# PT1003.net
KiCad netlist of a schematic drawn in Altium Designer
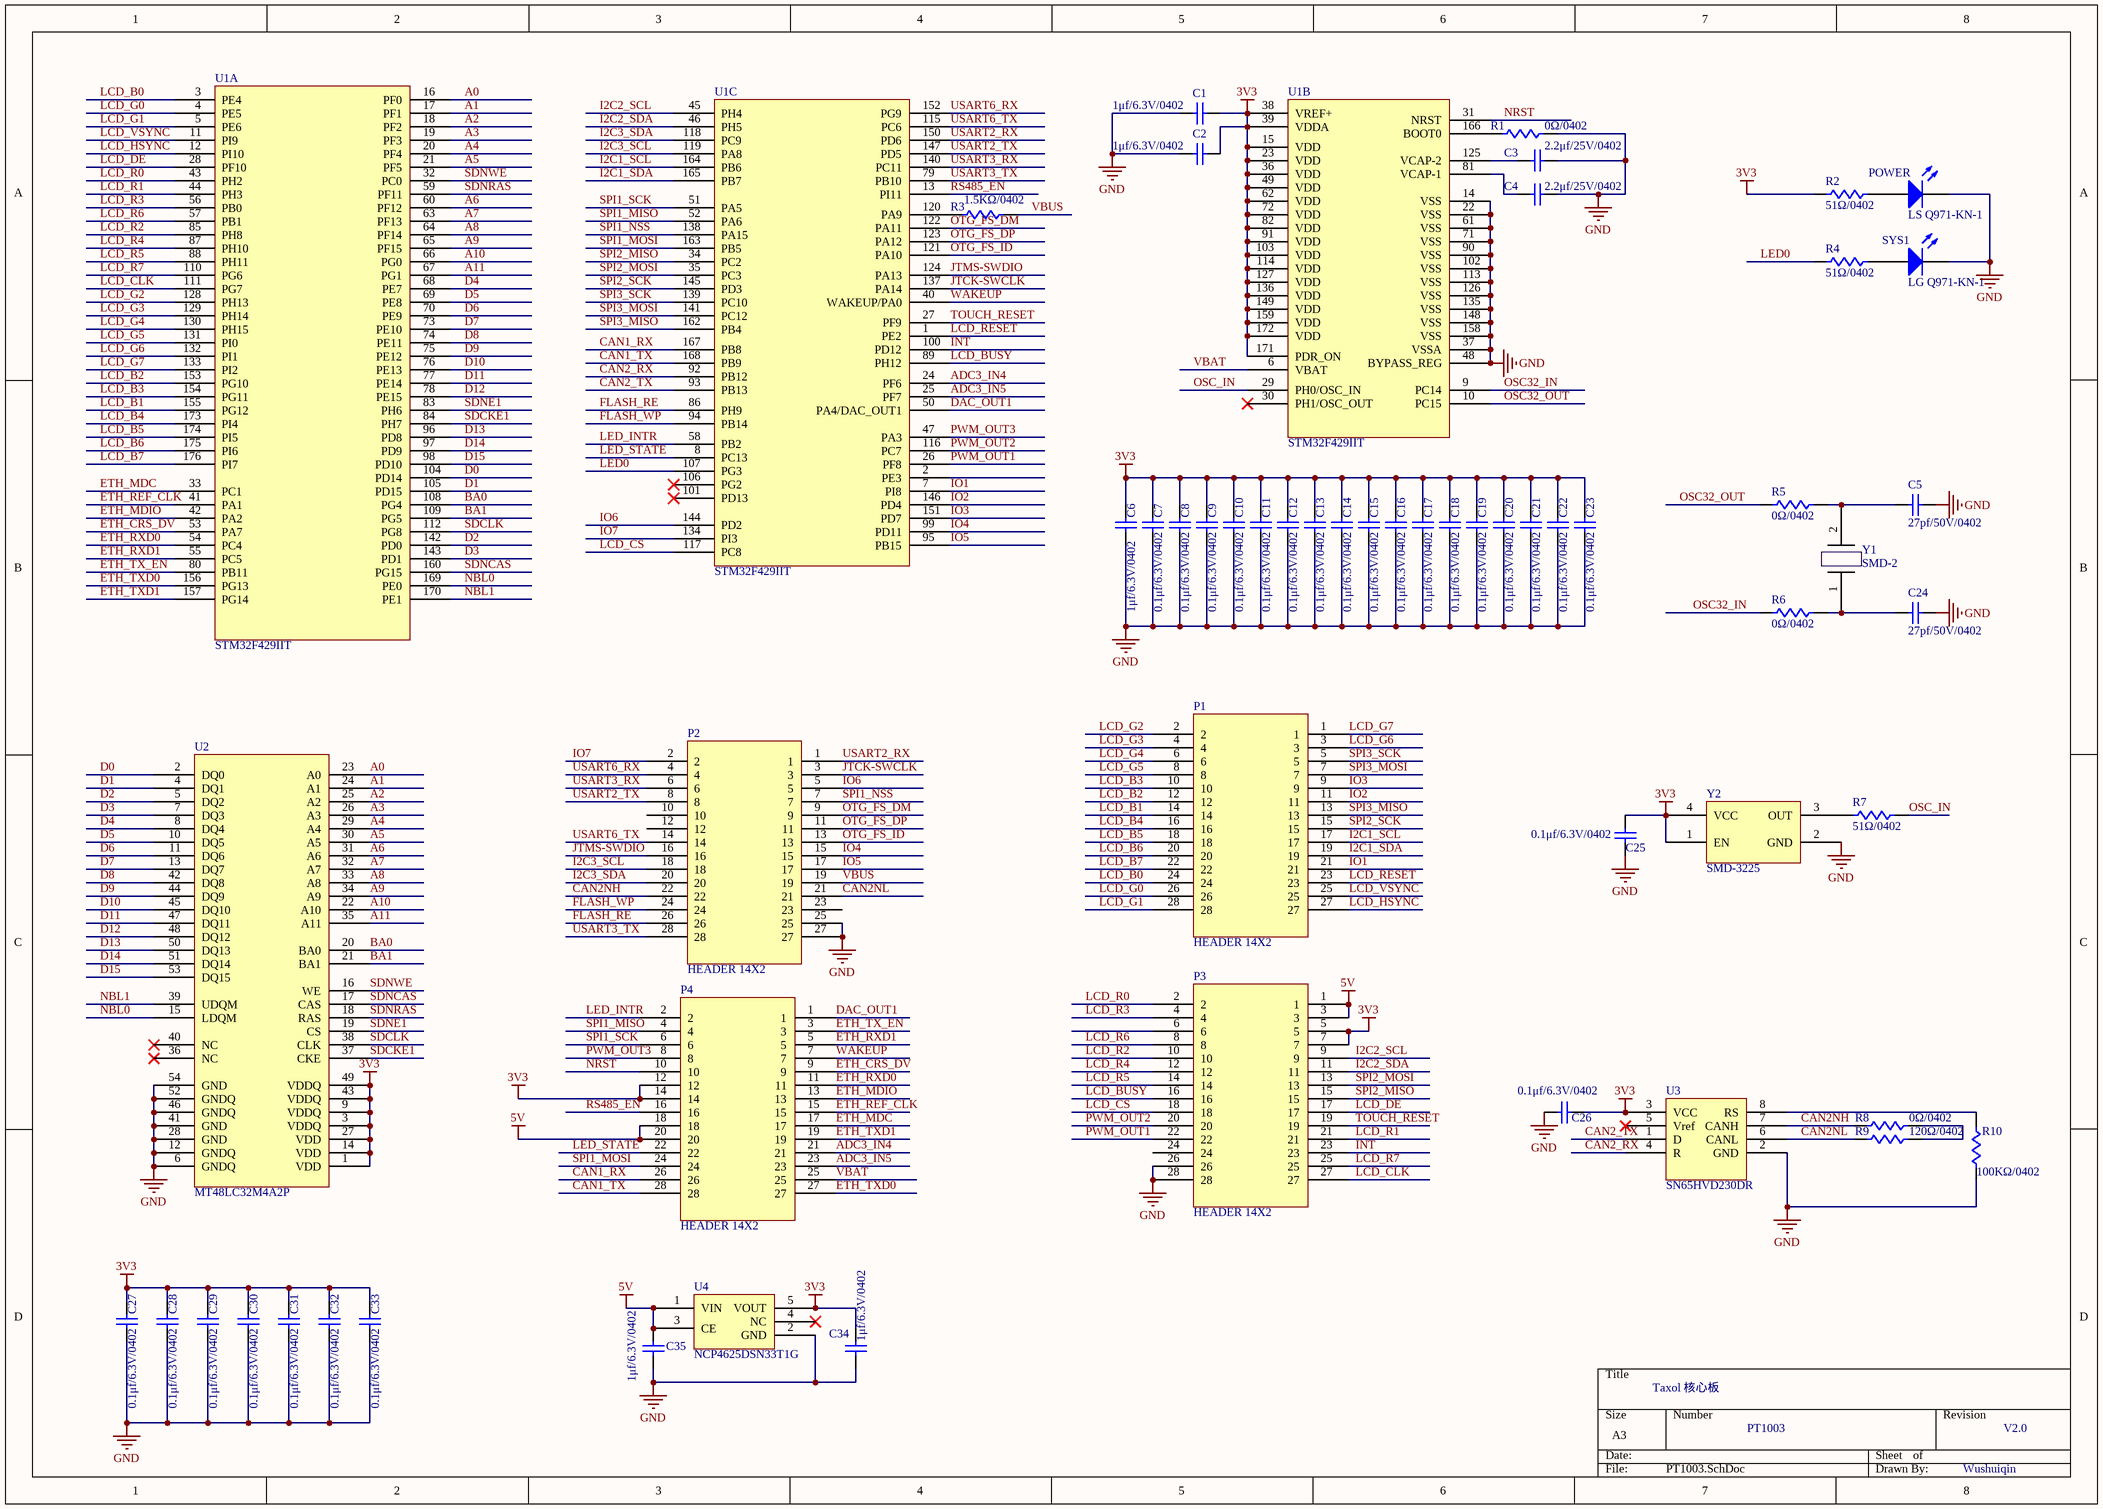
[diagram p0: PT1003.SchDoc]

(export (version "E")
  (design (tool "Eeschema 10.0.6"))
  (components
    (comp (ref "C1")
      (value "1μf/6.3V/0402")
      (footprint "CAPACITOR_0402")
      (fields (field (name "MANUFACTURER") "Murata"))
      (libsource (lib "Taxol") (part "CAPACITOR_0603"))
    )
    (comp (ref "C2")
      (value "1μf/6.3V/0402")
      (footprint "CAPACITOR_0402")
      (fields (field (name "MANUFACTURER") "Murata"))
      (libsource (lib "Taxol") (part "CAPACITOR_0603"))
    )
    (comp (ref "C3")
      (value "2.2μf/25V/0402")
      (footprint "CAPACITOR_0402")
      (fields (field (name "MANUFACTURER") "TDK"))
      (libsource (lib "Taxol") (part "CAPACITOR_0603"))
    )
    (comp (ref "C4")
      (value "2.2μf/25V/0402")
      (footprint "CAPACITOR_0402")
      (fields (field (name "MANUFACTURER") "TDK"))
      (libsource (lib "Taxol") (part "CAPACITOR_0603"))
    )
    (comp (ref "C5")
      (value "27pf/50V/0402")
      (footprint "CAPACITOR_0402")
      (fields (field (name "MANUFACTURER") "AVX"))
      (libsource (lib "PT1003") (part "CAPACITOR"))
    )
    (comp (ref "C6")
      (value "1μf/6.3V/0402")
      (footprint "CAPACITOR_0402")
      (fields (field (name "MANUFACTURER") "Murata"))
      (libsource (lib "Taxol") (part "CAPACITOR_0603"))
    )
    (comp (ref "C7")
      (value "0.1μf/6.3V/0402")
      (footprint "CAPACITOR_0402")
      (fields (field (name "MANUFACTURER") "TDK"))
      (libsource (lib "Taxol") (part "CAPACITOR_0603"))
    )
    (comp (ref "C8")
      (value "0.1μf/6.3V/0402")
      (footprint "CAPACITOR_0402")
      (fields (field (name "MANUFACTURER") "TDK"))
      (libsource (lib "Taxol") (part "CAPACITOR_0603"))
    )
    (comp (ref "C9")
      (value "0.1μf/6.3V/0402")
      (footprint "CAPACITOR_0402")
      (fields (field (name "MANUFACTURER") "TDK"))
      (libsource (lib "Taxol") (part "CAPACITOR_0603"))
    )
    (comp (ref "C10")
      (value "0.1μf/6.3V/0402")
      (footprint "CAPACITOR_0402")
      (fields (field (name "MANUFACTURER") "TDK"))
      (libsource (lib "Taxol") (part "CAPACITOR_0603"))
    )
    (comp (ref "C11")
      (value "0.1μf/6.3V/0402")
      (footprint "CAPACITOR_0402")
      (fields (field (name "MANUFACTURER") "TDK"))
      (libsource (lib "Taxol") (part "CAPACITOR_0603"))
    )
    (comp (ref "C12")
      (value "0.1μf/6.3V/0402")
      (footprint "CAPACITOR_0402")
      (fields (field (name "MANUFACTURER") "TDK"))
      (libsource (lib "Taxol") (part "CAPACITOR_0603"))
    )
    (comp (ref "C13")
      (value "0.1μf/6.3V/0402")
      (footprint "CAPACITOR_0402")
      (fields (field (name "MANUFACTURER") "TDK"))
      (libsource (lib "Taxol") (part "CAPACITOR_0603"))
    )
    (comp (ref "C14")
      (value "0.1μf/6.3V/0402")
      (footprint "CAPACITOR_0402")
      (fields (field (name "MANUFACTURER") "TDK"))
      (libsource (lib "Taxol") (part "CAPACITOR_0603"))
    )
    (comp (ref "C15")
      (value "0.1μf/6.3V/0402")
      (footprint "CAPACITOR_0402")
      (fields (field (name "MANUFACTURER") "TDK"))
      (libsource (lib "Taxol") (part "CAPACITOR_0603"))
    )
    (comp (ref "C16")
      (value "0.1μf/6.3V/0402")
      (footprint "CAPACITOR_0402")
      (fields (field (name "MANUFACTURER") "TDK"))
      (libsource (lib "Taxol") (part "CAPACITOR_0603"))
    )
    (comp (ref "C17")
      (value "0.1μf/6.3V/0402")
      (footprint "CAPACITOR_0402")
      (fields (field (name "MANUFACTURER") "TDK"))
      (libsource (lib "Taxol") (part "CAPACITOR_0603"))
    )
    (comp (ref "C18")
      (value "0.1μf/6.3V/0402")
      (footprint "CAPACITOR_0402")
      (fields (field (name "MANUFACTURER") "TDK"))
      (libsource (lib "Taxol") (part "CAPACITOR_0603"))
    )
    (comp (ref "C19")
      (value "0.1μf/6.3V/0402")
      (footprint "CAPACITOR_0402")
      (fields (field (name "MANUFACTURER") "TDK"))
      (libsource (lib "Taxol") (part "CAPACITOR_0603"))
    )
    (comp (ref "C20")
      (value "0.1μf/6.3V/0402")
      (footprint "CAPACITOR_0402")
      (fields (field (name "MANUFACTURER") "TDK"))
      (libsource (lib "Taxol") (part "CAPACITOR_0603"))
    )
    (comp (ref "C21")
      (value "0.1μf/6.3V/0402")
      (footprint "CAPACITOR_0402")
      (fields (field (name "MANUFACTURER") "TDK"))
      (libsource (lib "Taxol") (part "CAPACITOR_0603"))
    )
    (comp (ref "C22")
      (value "0.1μf/6.3V/0402")
      (footprint "CAPACITOR_0402")
      (fields (field (name "MANUFACTURER") "TDK"))
      (libsource (lib "Taxol") (part "CAPACITOR_0603"))
    )
    (comp (ref "C23")
      (value "0.1μf/6.3V/0402")
      (footprint "CAPACITOR_0402")
      (fields (field (name "MANUFACTURER") "TDK"))
      (libsource (lib "Taxol") (part "CAPACITOR_0603"))
    )
    (comp (ref "C24")
      (value "27pf/50V/0402")
      (footprint "CAPACITOR_0402")
      (fields (field (name "MANUFACTURER") "AVX"))
      (libsource (lib "PT1003") (part "CAPACITOR"))
    )
    (comp (ref "C25")
      (value "0.1μf/6.3V/0402")
      (footprint "CAPACITOR_0402")
      (fields (field (name "MANUFACTURER") "TDK"))
      (libsource (lib "Taxol") (part "CAPACITOR_0603"))
    )
    (comp (ref "C26")
      (value "0.1μf/6.3V/0402")
      (footprint "CAPACITOR_0402")
      (fields (field (name "MANUFACTURER") "TDK"))
      (libsource (lib "Taxol") (part "CAPACITOR_0603"))
    )
    (comp (ref "C27")
      (value "0.1μf/6.3V/0402")
      (footprint "CAPACITOR_0402")
      (fields (field (name "MANUFACTURER") "TDK"))
      (libsource (lib "Taxol") (part "CAPACITOR_0603"))
    )
    (comp (ref "C28")
      (value "0.1μf/6.3V/0402")
      (footprint "CAPACITOR_0402")
      (fields (field (name "MANUFACTURER") "TDK"))
      (libsource (lib "Taxol") (part "CAPACITOR_0603"))
    )
    (comp (ref "C29")
      (value "0.1μf/6.3V/0402")
      (footprint "CAPACITOR_0402")
      (fields (field (name "MANUFACTURER") "TDK"))
      (libsource (lib "Taxol") (part "CAPACITOR_0603"))
    )
    (comp (ref "C30")
      (value "0.1μf/6.3V/0402")
      (footprint "CAPACITOR_0402")
      (fields (field (name "MANUFACTURER") "TDK"))
      (libsource (lib "Taxol") (part "CAPACITOR_0603"))
    )
    (comp (ref "C31")
      (value "0.1μf/6.3V/0402")
      (footprint "CAPACITOR_0402")
      (fields (field (name "MANUFACTURER") "TDK"))
      (libsource (lib "Taxol") (part "CAPACITOR_0603"))
    )
    (comp (ref "C32")
      (value "0.1μf/6.3V/0402")
      (footprint "CAPACITOR_0402")
      (fields (field (name "MANUFACTURER") "TDK"))
      (libsource (lib "Taxol") (part "CAPACITOR_0603"))
    )
    (comp (ref "C33")
      (value "0.1μf/6.3V/0402")
      (footprint "CAPACITOR_0402")
      (fields (field (name "MANUFACTURER") "TDK"))
      (libsource (lib "Taxol") (part "CAPACITOR_0603"))
    )
    (comp (ref "C34")
      (value "1μf/6.3V/0402")
      (footprint "CAPACITOR_0402")
      (fields (field (name "MANUFACTURER") "Murata"))
      (libsource (lib "Taxol") (part "CAPACITOR_0603"))
    )
    (comp (ref "C35")
      (value "1μf/6.3V/0402")
      (footprint "CAPACITOR_0402")
      (fields (field (name "MANUFACTURER") "Murata"))
      (libsource (lib "Taxol") (part "CAPACITOR_0603"))
    )
    (comp (ref "P1") (value "HEADER 14X2") (footprint "PIN") (libsource (lib "PT1003") (part "PIN")))
    (comp (ref "P2") (value "HEADER 14X2") (footprint "PIN_1") (libsource (lib "PT1003") (part "PIN_1")))
    (comp (ref "P3") (value "HEADER 14X2") (footprint "PIN") (libsource (lib "PT1003") (part "PIN")))
    (comp (ref "P4") (value "HEADER 14X2") (footprint "PIN_1") (libsource (lib "PT1003") (part "PIN_1")))
    (comp (ref "POWER")
      (value "LS Q971-KN-1")
      (footprint "LED")
      (description "LED_G")
      (fields (field (name "MANUFACTURER") "OSRAM"))
      (libsource (lib "Taxol") (part "LED"))
    )
    (comp (ref "R1")
      (value "0Ω/0402")
      (footprint "RESSISTANCE_0402")
      (fields (field (name "MANUFACTURER") "VISHAY"))
      (libsource (lib "Taxol") (part "RESISTANCE"))
    )
    (comp (ref "R2")
      (value "51Ω/0402")
      (footprint "RESSISTANCE_0402")
      (fields (field (name "MANUFACTURER") "VISHAY"))
      (libsource (lib "Taxol") (part "RESISTANCE"))
    )
    (comp (ref "R3")
      (value "1.5KΩ/0402")
      (footprint "RESSISTANCE_0402")
      (fields (field (name "MANUFACTURER") "Vishay"))
      (libsource (lib "PT1003") (part "RESISTANCE"))
    )
    (comp (ref "R4")
      (value "51Ω/0402")
      (footprint "RESSISTANCE_0402")
      (fields (field (name "MANUFACTURER") "VISHAY"))
      (libsource (lib "Taxol") (part "RESISTANCE"))
    )
    (comp (ref "R5")
      (value "0Ω/0402")
      (footprint "RESSISTANCE_0402")
      (fields (field (name "MANUFACTURER") "VISHAY"))
      (libsource (lib "Taxol") (part "RESISTANCE"))
    )
    (comp (ref "R6")
      (value "0Ω/0402")
      (footprint "RESSISTANCE_0402")
      (fields (field (name "MANUFACTURER") "Vishay"))
      (libsource (lib "PT1003") (part "RESISTANCE"))
    )
    (comp (ref "R7")
      (value "51Ω/0402")
      (footprint "RESSISTANCE_0402")
      (fields (field (name "MANUFACTURER") "VISHAY"))
      (libsource (lib "Taxol") (part "RESISTANCE"))
    )
    (comp (ref "R8")
      (value "0Ω/0402")
      (footprint "RESSISTANCE_0402")
      (fields (field (name "MANUFACTURER") "VISHAY"))
      (libsource (lib "PT1003") (part "RESISTANCE"))
    )
    (comp (ref "R9")
      (value "120Ω/0402")
      (footprint "RESSISTANCE_0402")
      (fields (field (name "MANUFACTURER") "Vishay"))
      (libsource (lib "PT1003") (part "RESISTANCE"))
    )
    (comp (ref "R10")
      (value "100KΩ/0402")
      (footprint "RESSISTANCE_0402")
      (fields (field (name "MANUFACTURER") "VISHAY"))
      (libsource (lib "Taxol") (part "RESISTANCE"))
    )
    (comp (ref "SYS1")
      (value "LG Q971-KN-1")
      (footprint "LED")
      (description "LED_G")
      (fields (field (name "MANUFACTURER") "OSRAM"))
      (libsource (lib "Taxol") (part "LED"))
    )
    (comp (ref "U1")
      (value "STM32F429IIT")
      (footprint "STM32F429IIT")
      (fields (field (name "MANUFACTURER") "ST"))
      (libsource (lib "PT1003") (part "STM32F429IIT"))
    )
    (comp (ref "U2")
      (value "MT48LC32M4A2P")
      (footprint "IS42S16400J")
      (description "SDRAM")
      (fields (field (name "MANUFACTURER") "MICRON"))
      (libsource (lib "PT1003") (part "IS42S16400J"))
    )
    (comp (ref "U3")
      (value "SN65HVD230DR")
      (footprint "SN65HVD230")
      (description "CAN")
      (fields (field (name "MANUFACTURER") "TEXAS INSTRUMENTS"))
      (libsource (lib "Taxol") (part "SN65HVD230DR"))
    )
    (comp (ref "U4")
      (value "NCP4625DSN33T1G")
      (footprint "NCP4625DSN33T1G")
      (fields (field (name "MANUFACTURER") "ON"))
      (libsource (lib "PT1003") (part "NCP4625DSN33T1G"))
    )
    (comp (ref "Y1")
      (value "SMD-2")
      (footprint "SMD-2")
      (fields (field (name "MANUFACTURER") "MICRO CRYSTAL SWITZERLAND"))
      (libsource (lib "PT1003") (part "CC7V-TIA"))
    )
    (comp (ref "Y2")
      (value "SMD-3225")
      (footprint "X032")
      (description "4-Pin")
      (fields (field (name "MANUFACTURER") "深圳市金丰瑞电子有限公司"))
      (libsource (lib "Taxol") (part "X075_8MHZ"))
    )
  )
  (nets
    (net (code "1") (name "/A0") (class "Default")
      (node (ref "U1") (pin "16") (pinfunction "PF0_16") (pintype "passive"))
      (node (ref "U2") (pin "23") (pinfunction "A0_23") (pintype "passive"))
    )
    (net (code "2") (name "/A1") (class "Default")
      (node (ref "U1") (pin "17") (pinfunction "PF1_17") (pintype "passive"))
      (node (ref "U2") (pin "24") (pinfunction "A1_24") (pintype "passive"))
    )
    (net (code "3") (name "/A2") (class "Default")
      (node (ref "U1") (pin "18") (pinfunction "PF2_18") (pintype "passive"))
      (node (ref "U2") (pin "25") (pinfunction "A2_25") (pintype "passive"))
    )
    (net (code "4") (name "/A3") (class "Default")
      (node (ref "U1") (pin "19") (pinfunction "PF3_19") (pintype "passive"))
      (node (ref "U2") (pin "26") (pinfunction "A3_26") (pintype "passive"))
    )
    (net (code "5") (name "/A4") (class "Default")
      (node (ref "U1") (pin "20") (pinfunction "PF4_20") (pintype "passive"))
      (node (ref "U2") (pin "29") (pinfunction "A4_29") (pintype "passive"))
    )
    (net (code "6") (name "/A5") (class "Default")
      (node (ref "U1") (pin "21") (pinfunction "PF5_21") (pintype "passive"))
      (node (ref "U2") (pin "30") (pinfunction "A5_30") (pintype "passive"))
    )
    (net (code "7") (name "/A6") (class "Default")
      (node (ref "U1") (pin "60") (pinfunction "PF12_60") (pintype "passive"))
      (node (ref "U2") (pin "31") (pinfunction "A6_31") (pintype "passive"))
    )
    (net (code "8") (name "/A7") (class "Default")
      (node (ref "U1") (pin "63") (pinfunction "PF13_63") (pintype "passive"))
      (node (ref "U2") (pin "32") (pinfunction "A7_32") (pintype "passive"))
    )
    (net (code "9") (name "/A8") (class "Default")
      (node (ref "U1") (pin "64") (pinfunction "PF14_64") (pintype "passive"))
      (node (ref "U2") (pin "33") (pinfunction "A8_33") (pintype "passive"))
    )
    (net (code "10") (name "/A9") (class "Default")
      (node (ref "U1") (pin "65") (pinfunction "PF15_65") (pintype "passive"))
      (node (ref "U2") (pin "34") (pinfunction "A9_34") (pintype "passive"))
    )
    (net (code "11") (name "/A10") (class "Default")
      (node (ref "U1") (pin "66") (pinfunction "PG0_66") (pintype "passive"))
      (node (ref "U2") (pin "22") (pinfunction "A10_22") (pintype "passive"))
    )
    (net (code "12") (name "/A11") (class "Default")
      (node (ref "U1") (pin "67") (pinfunction "PG1_67") (pintype "passive"))
      (node (ref "U2") (pin "35") (pinfunction "A11_35") (pintype "passive"))
    )
    (net (code "13") (name "/ADC3_IN4") (class "Default")
      (node (ref "P4") (pin "21") (pinfunction "21_21") (pintype "passive"))
      (node (ref "U1") (pin "24") (pinfunction "PF6_24") (pintype "passive"))
    )
    (net (code "14") (name "/ADC3_IN5") (class "Default")
      (node (ref "P4") (pin "23") (pinfunction "23_23") (pintype "passive"))
      (node (ref "U1") (pin "25") (pinfunction "PF7_25") (pintype "passive"))
    )
    (net (code "15") (name "/BA0") (class "Default")
      (node (ref "U1") (pin "108") (pinfunction "PG4_108") (pintype "passive"))
      (node (ref "U2") (pin "20") (pinfunction "BA0_20") (pintype "passive"))
    )
    (net (code "16") (name "/BA1") (class "Default")
      (node (ref "U1") (pin "109") (pinfunction "PG5_109") (pintype "passive"))
      (node (ref "U2") (pin "21") (pinfunction "BA1_21") (pintype "passive"))
    )
    (net (code "17") (name "/CAN1_RX") (class "Default")
      (node (ref "P4") (pin "26") (pinfunction "26_26") (pintype "passive"))
      (node (ref "U1") (pin "167") (pinfunction "PB8_167") (pintype "passive"))
    )
    (net (code "18") (name "/CAN1_TX") (class "Default")
      (node (ref "P4") (pin "28") (pinfunction "28_28") (pintype "passive"))
      (node (ref "U1") (pin "168") (pinfunction "PB9_168") (pintype "passive"))
    )
    (net (code "19") (name "/CAN2NH") (class "Default")
      (node (ref "P2") (pin "22") (pinfunction "22_22") (pintype "passive"))
      (node (ref "R8") (pin "1") (pinfunction "1_1") (pintype "passive"))
      (node (ref "U3") (pin "7") (pinfunction "CANH_7") (pintype "passive"))
    )
    (net (code "20") (name "/CAN2NL") (class "Default")
      (node (ref "P2") (pin "21") (pinfunction "21_21") (pintype "passive"))
      (node (ref "R9") (pin "1") (pinfunction "1_1") (pintype "passive"))
      (node (ref "U3") (pin "6") (pinfunction "CANL_6") (pintype "passive"))
    )
    (net (code "21") (name "/CAN2_RX") (class "Default")
      (node (ref "U1") (pin "92") (pinfunction "PB12_92") (pintype "passive"))
      (node (ref "U3") (pin "4") (pinfunction "R_4") (pintype "passive"))
    )
    (net (code "22") (name "/CAN2_TX") (class "Default")
      (node (ref "U1") (pin "93") (pinfunction "PB13_93") (pintype "passive"))
      (node (ref "U3") (pin "1") (pinfunction "D_1") (pintype "passive"))
    )
    (net (code "23") (name "/D0") (class "Default")
      (node (ref "U1") (pin "104") (pinfunction "PD14_104") (pintype "passive"))
      (node (ref "U2") (pin "2") (pinfunction "DQ0_2") (pintype "passive"))
    )
    (net (code "24") (name "/D1") (class "Default")
      (node (ref "U1") (pin "105") (pinfunction "PD15_105") (pintype "passive"))
      (node (ref "U2") (pin "4") (pinfunction "DQ1_4") (pintype "passive"))
    )
    (net (code "25") (name "/D2") (class "Default")
      (node (ref "U1") (pin "142") (pinfunction "PD0_142") (pintype "passive"))
      (node (ref "U2") (pin "5") (pinfunction "DQ2_5") (pintype "passive"))
    )
    (net (code "26") (name "/D3") (class "Default")
      (node (ref "U1") (pin "143") (pinfunction "PD1_143") (pintype "passive"))
      (node (ref "U2") (pin "7") (pinfunction "DQ3_7") (pintype "passive"))
    )
    (net (code "27") (name "/D4") (class "Default")
      (node (ref "U1") (pin "68") (pinfunction "PE7_68") (pintype "passive"))
      (node (ref "U2") (pin "8") (pinfunction "DQ4_8") (pintype "passive"))
    )
    (net (code "28") (name "/D5") (class "Default")
      (node (ref "U1") (pin "69") (pinfunction "PE8_69") (pintype "passive"))
      (node (ref "U2") (pin "10") (pinfunction "DQ5_10") (pintype "passive"))
    )
    (net (code "29") (name "/D6") (class "Default")
      (node (ref "U1") (pin "70") (pinfunction "PE9_70") (pintype "passive"))
      (node (ref "U2") (pin "11") (pinfunction "DQ6_11") (pintype "passive"))
    )
    (net (code "30") (name "/D7") (class "Default")
      (node (ref "U1") (pin "73") (pinfunction "PE10_73") (pintype "passive"))
      (node (ref "U2") (pin "13") (pinfunction "DQ7_13") (pintype "passive"))
    )
    (net (code "31") (name "/D8") (class "Default")
      (node (ref "U1") (pin "74") (pinfunction "PE11_74") (pintype "passive"))
      (node (ref "U2") (pin "42") (pinfunction "DQ8_42") (pintype "passive"))
    )
    (net (code "32") (name "/D9") (class "Default")
      (node (ref "U1") (pin "75") (pinfunction "PE12_75") (pintype "passive"))
      (node (ref "U2") (pin "44") (pinfunction "DQ9_44") (pintype "passive"))
    )
    (net (code "33") (name "/D10") (class "Default")
      (node (ref "U1") (pin "76") (pinfunction "PE13_76") (pintype "passive"))
      (node (ref "U2") (pin "45") (pinfunction "DQ10_45") (pintype "passive"))
    )
    (net (code "34") (name "/D11") (class "Default")
      (node (ref "U1") (pin "77") (pinfunction "PE14_77") (pintype "passive"))
      (node (ref "U2") (pin "47") (pinfunction "DQ11_47") (pintype "passive"))
    )
    (net (code "35") (name "/D12") (class "Default")
      (node (ref "U1") (pin "78") (pinfunction "PE15_78") (pintype "passive"))
      (node (ref "U2") (pin "48") (pinfunction "DQ12_48") (pintype "passive"))
    )
    (net (code "36") (name "/D13") (class "Default")
      (node (ref "U1") (pin "96") (pinfunction "PD8_96") (pintype "passive"))
      (node (ref "U2") (pin "50") (pinfunction "DQ13_50") (pintype "passive"))
    )
    (net (code "37") (name "/D14") (class "Default")
      (node (ref "U1") (pin "97") (pinfunction "PD9_97") (pintype "passive"))
      (node (ref "U2") (pin "51") (pinfunction "DQ14_51") (pintype "passive"))
    )
    (net (code "38") (name "/D15") (class "Default")
      (node (ref "U1") (pin "98") (pinfunction "PD10_98") (pintype "passive"))
      (node (ref "U2") (pin "53") (pinfunction "DQ15_53") (pintype "passive"))
    )
    (net (code "39") (name "/DAC_OUT1") (class "Default")
      (node (ref "P4") (pin "1") (pinfunction "1_1") (pintype "passive"))
      (node (ref "U1") (pin "50") (pinfunction "PA4/DAC_OUT1_50") (pintype "passive"))
    )
    (net (code "40") (name "/ETH_CRS_DV") (class "Default")
      (node (ref "P4") (pin "9") (pinfunction "9_9") (pintype "passive"))
      (node (ref "U1") (pin "53") (pinfunction "PA7_53") (pintype "passive"))
    )
    (net (code "41") (name "/ETH_MDC") (class "Default")
      (node (ref "P4") (pin "17") (pinfunction "17_17") (pintype "passive"))
      (node (ref "U1") (pin "33") (pinfunction "PC1_33") (pintype "passive"))
    )
    (net (code "42") (name "/ETH_MDIO") (class "Default")
      (node (ref "P4") (pin "13") (pinfunction "13_13") (pintype "passive"))
      (node (ref "U1") (pin "42") (pinfunction "PA2_42") (pintype "passive"))
    )
    (net (code "43") (name "/ETH_REF_CLK") (class "Default")
      (node (ref "P4") (pin "15") (pinfunction "15_15") (pintype "passive"))
      (node (ref "U1") (pin "41") (pinfunction "PA1_41") (pintype "passive"))
    )
    (net (code "44") (name "/ETH_RXD0") (class "Default")
      (node (ref "P4") (pin "11") (pinfunction "11_11") (pintype "passive"))
      (node (ref "U1") (pin "54") (pinfunction "PC4_54") (pintype "passive"))
    )
    (net (code "45") (name "/ETH_RXD1") (class "Default")
      (node (ref "P4") (pin "5") (pinfunction "5_5") (pintype "passive"))
      (node (ref "U1") (pin "55") (pinfunction "PC5_55") (pintype "passive"))
    )
    (net (code "46") (name "/ETH_TXD0") (class "Default")
      (node (ref "P4") (pin "27") (pinfunction "27_27") (pintype "passive"))
      (node (ref "U1") (pin "156") (pinfunction "PG13_156") (pintype "passive"))
    )
    (net (code "47") (name "/ETH_TXD1") (class "Default")
      (node (ref "P4") (pin "19") (pinfunction "19_19") (pintype "passive"))
      (node (ref "U1") (pin "157") (pinfunction "PG14_157") (pintype "passive"))
    )
    (net (code "48") (name "/ETH_TX_EN") (class "Default")
      (node (ref "P4") (pin "3") (pinfunction "3_3") (pintype "passive"))
      (node (ref "U1") (pin "80") (pinfunction "PB11_80") (pintype "passive"))
    )
    (net (code "49") (name "/FLASH_RE") (class "Default")
      (node (ref "P2") (pin "26") (pinfunction "26_26") (pintype "passive"))
      (node (ref "U1") (pin "86") (pinfunction "PH9_86") (pintype "passive"))
    )
    (net (code "50") (name "/FLASH_WP") (class "Default")
      (node (ref "P2") (pin "24") (pinfunction "24_24") (pintype "passive"))
      (node (ref "U1") (pin "94") (pinfunction "PB14_94") (pintype "passive"))
    )
    (net (code "51") (name "/I2C1_SCL") (class "Default")
      (node (ref "P1") (pin "17") (pinfunction "17_17") (pintype "passive"))
      (node (ref "U1") (pin "164") (pinfunction "PB6_164") (pintype "passive"))
    )
    (net (code "52") (name "/I2C1_SDA") (class "Default")
      (node (ref "P1") (pin "19") (pinfunction "19_19") (pintype "passive"))
      (node (ref "U1") (pin "165") (pinfunction "PB7_165") (pintype "passive"))
    )
    (net (code "53") (name "/I2C2_SCL") (class "Default")
      (node (ref "P3") (pin "9") (pinfunction "9_9") (pintype "passive"))
      (node (ref "U1") (pin "45") (pinfunction "PH4_45") (pintype "passive"))
    )
    (net (code "54") (name "/I2C2_SDA") (class "Default")
      (node (ref "P3") (pin "11") (pinfunction "11_11") (pintype "passive"))
      (node (ref "U1") (pin "46") (pinfunction "PH5_46") (pintype "passive"))
    )
    (net (code "55") (name "/I2C3_SCL") (class "Default")
      (node (ref "P2") (pin "18") (pinfunction "18_18") (pintype "passive"))
      (node (ref "U1") (pin "119") (pinfunction "PA8_119") (pintype "passive"))
    )
    (net (code "56") (name "/I2C3_SDA") (class "Default")
      (node (ref "P2") (pin "20") (pinfunction "20_20") (pintype "passive"))
      (node (ref "U1") (pin "118") (pinfunction "PC9_118") (pintype "passive"))
    )
    (net (code "57") (name "/INT") (class "Default")
      (node (ref "P3") (pin "23") (pinfunction "23_23") (pintype "passive"))
      (node (ref "U1") (pin "100") (pinfunction "PD12_100") (pintype "passive"))
    )
    (net (code "58") (name "/IO1") (class "Default")
      (node (ref "P1") (pin "21") (pinfunction "21_21") (pintype "passive"))
      (node (ref "U1") (pin "7") (pinfunction "PI8_7") (pintype "passive"))
    )
    (net (code "59") (name "/IO2") (class "Default")
      (node (ref "P1") (pin "11") (pinfunction "11_11") (pintype "passive"))
      (node (ref "U1") (pin "146") (pinfunction "PD4_146") (pintype "passive"))
    )
    (net (code "60") (name "/IO3") (class "Default")
      (node (ref "P1") (pin "9") (pinfunction "9_9") (pintype "passive"))
      (node (ref "U1") (pin "151") (pinfunction "PD7_151") (pintype "passive"))
    )
    (net (code "61") (name "/IO4") (class "Default")
      (node (ref "P2") (pin "15") (pinfunction "15_15") (pintype "passive"))
      (node (ref "U1") (pin "99") (pinfunction "PD11_99") (pintype "passive"))
    )
    (net (code "62") (name "/IO5") (class "Default")
      (node (ref "P2") (pin "17") (pinfunction "17_17") (pintype "passive"))
      (node (ref "U1") (pin "95") (pinfunction "PB15_95") (pintype "passive"))
    )
    (net (code "63") (name "/IO6") (class "Default")
      (node (ref "P2") (pin "5") (pinfunction "5_5") (pintype "passive"))
      (node (ref "U1") (pin "144") (pinfunction "PD2_144") (pintype "passive"))
    )
    (net (code "64") (name "/IO7") (class "Default")
      (node (ref "P2") (pin "2") (pinfunction "2_2") (pintype "passive"))
      (node (ref "U1") (pin "134") (pinfunction "PI3_134") (pintype "passive"))
    )
    (net (code "65") (name "/JTCK-SWCLK") (class "Default")
      (node (ref "P2") (pin "3") (pinfunction "3_3") (pintype "passive"))
      (node (ref "U1") (pin "137") (pinfunction "PA14_137") (pintype "passive"))
    )
    (net (code "66") (name "/JTMS-SWDIO") (class "Default")
      (node (ref "P2") (pin "16") (pinfunction "16_16") (pintype "passive"))
      (node (ref "U1") (pin "124") (pinfunction "PA13_124") (pintype "passive"))
    )
    (net (code "67") (name "/LCD_B0") (class "Default")
      (node (ref "P1") (pin "24") (pinfunction "24_24") (pintype "passive"))
      (node (ref "U1") (pin "3") (pinfunction "PE4_3") (pintype "passive"))
    )
    (net (code "68") (name "/LCD_B1") (class "Default")
      (node (ref "P1") (pin "14") (pinfunction "14_14") (pintype "passive"))
      (node (ref "U1") (pin "155") (pinfunction "PG12_155") (pintype "passive"))
    )
    (net (code "69") (name "/LCD_B2") (class "Default")
      (node (ref "P1") (pin "12") (pinfunction "12_12") (pintype "passive"))
      (node (ref "U1") (pin "153") (pinfunction "PG10_153") (pintype "passive"))
    )
    (net (code "70") (name "/LCD_B3") (class "Default")
      (node (ref "P1") (pin "10") (pinfunction "10_10") (pintype "passive"))
      (node (ref "U1") (pin "154") (pinfunction "PG11_154") (pintype "passive"))
    )
    (net (code "71") (name "/LCD_B4") (class "Default")
      (node (ref "P1") (pin "16") (pinfunction "16_16") (pintype "passive"))
      (node (ref "U1") (pin "173") (pinfunction "PI4_173") (pintype "passive"))
    )
    (net (code "72") (name "/LCD_B5") (class "Default")
      (node (ref "P1") (pin "18") (pinfunction "18_18") (pintype "passive"))
      (node (ref "U1") (pin "174") (pinfunction "PI5_174") (pintype "passive"))
    )
    (net (code "73") (name "/LCD_B6") (class "Default")
      (node (ref "P1") (pin "20") (pinfunction "20_20") (pintype "passive"))
      (node (ref "U1") (pin "175") (pinfunction "PI6_175") (pintype "passive"))
    )
    (net (code "74") (name "/LCD_B7") (class "Default")
      (node (ref "P1") (pin "22") (pinfunction "22_22") (pintype "passive"))
      (node (ref "U1") (pin "176") (pinfunction "PI7_176") (pintype "passive"))
    )
    (net (code "75") (name "/LCD_BUSY") (class "Default")
      (node (ref "P3") (pin "16") (pinfunction "16_16") (pintype "passive"))
      (node (ref "U1") (pin "89") (pinfunction "PH12_89") (pintype "passive"))
    )
    (net (code "76") (name "/LCD_CLK") (class "Default")
      (node (ref "P3") (pin "27") (pinfunction "27_27") (pintype "passive"))
      (node (ref "U1") (pin "111") (pinfunction "PG7_111") (pintype "passive"))
    )
    (net (code "77") (name "/LCD_CS") (class "Default")
      (node (ref "P3") (pin "18") (pinfunction "18_18") (pintype "passive"))
      (node (ref "U1") (pin "117") (pinfunction "PC8_117") (pintype "passive"))
    )
    (net (code "78") (name "/LCD_DE") (class "Default")
      (node (ref "P3") (pin "17") (pinfunction "17_17") (pintype "passive"))
      (node (ref "U1") (pin "28") (pinfunction "PF10_28") (pintype "passive"))
    )
    (net (code "79") (name "/LCD_G0") (class "Default")
      (node (ref "P1") (pin "26") (pinfunction "26_26") (pintype "passive"))
      (node (ref "U1") (pin "4") (pinfunction "PE5_4") (pintype "passive"))
    )
    (net (code "80") (name "/LCD_G1") (class "Default")
      (node (ref "P1") (pin "28") (pinfunction "28_28") (pintype "passive"))
      (node (ref "U1") (pin "5") (pinfunction "PE6_5") (pintype "passive"))
    )
    (net (code "81") (name "/LCD_G2") (class "Default")
      (node (ref "P1") (pin "2") (pinfunction "2_2") (pintype "passive"))
      (node (ref "U1") (pin "128") (pinfunction "PH13_128") (pintype "passive"))
    )
    (net (code "82") (name "/LCD_G3") (class "Default")
      (node (ref "P1") (pin "4") (pinfunction "4_4") (pintype "passive"))
      (node (ref "U1") (pin "129") (pinfunction "PH14_129") (pintype "passive"))
    )
    (net (code "83") (name "/LCD_G4") (class "Default")
      (node (ref "P1") (pin "6") (pinfunction "6_6") (pintype "passive"))
      (node (ref "U1") (pin "130") (pinfunction "PH15_130") (pintype "passive"))
    )
    (net (code "84") (name "/LCD_G5") (class "Default")
      (node (ref "P1") (pin "8") (pinfunction "8_8") (pintype "passive"))
      (node (ref "U1") (pin "131") (pinfunction "PI0_131") (pintype "passive"))
    )
    (net (code "85") (name "/LCD_G6") (class "Default")
      (node (ref "P1") (pin "3") (pinfunction "3_3") (pintype "passive"))
      (node (ref "U1") (pin "132") (pinfunction "PI1_132") (pintype "passive"))
    )
    (net (code "86") (name "/LCD_G7") (class "Default")
      (node (ref "P1") (pin "1") (pinfunction "1_1") (pintype "passive"))
      (node (ref "U1") (pin "133") (pinfunction "PI2_133") (pintype "passive"))
    )
    (net (code "87") (name "/LCD_HSYNC") (class "Default")
      (node (ref "P1") (pin "27") (pinfunction "27_27") (pintype "passive"))
      (node (ref "U1") (pin "12") (pinfunction "PI10_12") (pintype "passive"))
    )
    (net (code "88") (name "/LCD_R0") (class "Default")
      (node (ref "P3") (pin "2") (pinfunction "2_2") (pintype "passive"))
      (node (ref "U1") (pin "43") (pinfunction "PH2_43") (pintype "passive"))
    )
    (net (code "89") (name "/LCD_R1") (class "Default")
      (node (ref "P3") (pin "21") (pinfunction "21_21") (pintype "passive"))
      (node (ref "U1") (pin "44") (pinfunction "PH3_44") (pintype "passive"))
    )
    (net (code "90") (name "/LCD_R2") (class "Default")
      (node (ref "P3") (pin "10") (pinfunction "10_10") (pintype "passive"))
      (node (ref "U1") (pin "85") (pinfunction "PH8_85") (pintype "passive"))
    )
    (net (code "91") (name "/LCD_R3") (class "Default")
      (node (ref "P3") (pin "4") (pinfunction "4_4") (pintype "passive"))
      (node (ref "U1") (pin "56") (pinfunction "PB0_56") (pintype "passive"))
    )
    (net (code "92") (name "/LCD_R4") (class "Default")
      (node (ref "P3") (pin "12") (pinfunction "12_12") (pintype "passive"))
      (node (ref "U1") (pin "87") (pinfunction "PH10_87") (pintype "passive"))
    )
    (net (code "93") (name "/LCD_R5") (class "Default")
      (node (ref "P3") (pin "14") (pinfunction "14_14") (pintype "passive"))
      (node (ref "U1") (pin "88") (pinfunction "PH11_88") (pintype "passive"))
    )
    (net (code "94") (name "/LCD_R6") (class "Default")
      (node (ref "P3") (pin "8") (pinfunction "8_8") (pintype "passive"))
      (node (ref "U1") (pin "57") (pinfunction "PB1_57") (pintype "passive"))
    )
    (net (code "95") (name "/LCD_R7") (class "Default")
      (node (ref "P3") (pin "25") (pinfunction "25_25") (pintype "passive"))
      (node (ref "U1") (pin "110") (pinfunction "PG6_110") (pintype "passive"))
    )
    (net (code "96") (name "/LCD_RESET") (class "Default")
      (node (ref "P1") (pin "23") (pinfunction "23_23") (pintype "passive"))
      (node (ref "U1") (pin "1") (pinfunction "PE2_1") (pintype "passive"))
    )
    (net (code "97") (name "/LCD_VSYNC") (class "Default")
      (node (ref "P1") (pin "25") (pinfunction "25_25") (pintype "passive"))
      (node (ref "U1") (pin "11") (pinfunction "PI9_11") (pintype "passive"))
    )
    (net (code "98") (name "/LED0") (class "Default")
      (node (ref "R4") (pin "1") (pinfunction "1_1") (pintype "passive"))
      (node (ref "U1") (pin "107") (pinfunction "PG3_107") (pintype "passive"))
    )
    (net (code "99") (name "/LED_INTR") (class "Default")
      (node (ref "P4") (pin "2") (pinfunction "2_2") (pintype "passive"))
      (node (ref "U1") (pin "58") (pinfunction "PB2_58") (pintype "passive"))
    )
    (net (code "100") (name "/LED_STATE") (class "Default")
      (node (ref "P4") (pin "22") (pinfunction "22_22") (pintype "passive"))
      (node (ref "U1") (pin "8") (pinfunction "PC13_8") (pintype "passive"))
    )
    (net (code "101") (name "/NBL0") (class "Default")
      (node (ref "U1") (pin "169") (pinfunction "PE0_169") (pintype "passive"))
      (node (ref "U2") (pin "15") (pinfunction "LDQM_15") (pintype "passive"))
    )
    (net (code "102") (name "/NBL1") (class "Default")
      (node (ref "U1") (pin "170") (pinfunction "PE1_170") (pintype "passive"))
      (node (ref "U2") (pin "39") (pinfunction "UDQM_39") (pintype "passive"))
    )
    (net (code "103") (name "/NRST") (class "Default")
      (node (ref "P4") (pin "10") (pinfunction "10_10") (pintype "passive"))
      (node (ref "U1") (pin "31") (pinfunction "NRST_31") (pintype "passive"))
    )
    (net (code "104") (name "/OSC32_IN") (class "Default")
      (node (ref "R6") (pin "1") (pinfunction "1_1") (pintype "passive"))
      (node (ref "U1") (pin "9") (pinfunction "PC14_9") (pintype "passive"))
    )
    (net (code "105") (name "/OSC32_OUT") (class "Default")
      (node (ref "R5") (pin "1") (pinfunction "1_1") (pintype "passive"))
      (node (ref "U1") (pin "10") (pinfunction "PC15_10") (pintype "passive"))
    )
    (net (code "106") (name "/OSC_IN") (class "Default")
      (node (ref "R7") (pin "2") (pinfunction "2_2") (pintype "passive"))
      (node (ref "U1") (pin "29") (pinfunction "PH0/OSC_IN_29") (pintype "passive"))
    )
    (net (code "107") (name "/OTG_FS_DM") (class "Default")
      (node (ref "P2") (pin "9") (pinfunction "9_9") (pintype "passive"))
      (node (ref "U1") (pin "122") (pinfunction "PA11_122") (pintype "passive"))
    )
    (net (code "108") (name "/OTG_FS_DP") (class "Default")
      (node (ref "P2") (pin "11") (pinfunction "11_11") (pintype "passive"))
      (node (ref "U1") (pin "123") (pinfunction "PA12_123") (pintype "passive"))
    )
    (net (code "109") (name "/OTG_FS_ID") (class "Default")
      (node (ref "P2") (pin "13") (pinfunction "13_13") (pintype "passive"))
      (node (ref "U1") (pin "121") (pinfunction "PA10_121") (pintype "passive"))
    )
    (net (code "110") (name "/PWM_OUT1") (class "Default")
      (node (ref "P3") (pin "22") (pinfunction "22_22") (pintype "passive"))
      (node (ref "U1") (pin "26") (pinfunction "PF8_26") (pintype "passive"))
    )
    (net (code "111") (name "/PWM_OUT2") (class "Default")
      (node (ref "P3") (pin "20") (pinfunction "20_20") (pintype "passive"))
      (node (ref "U1") (pin "116") (pinfunction "PC7_116") (pintype "passive"))
    )
    (net (code "112") (name "/PWM_OUT3") (class "Default")
      (node (ref "P4") (pin "8") (pinfunction "8_8") (pintype "passive"))
      (node (ref "U1") (pin "47") (pinfunction "PA3_47") (pintype "passive"))
    )
    (net (code "113") (name "/RS485_EN") (class "Default")
      (node (ref "P4") (pin "16") (pinfunction "16_16") (pintype "passive"))
      (node (ref "U1") (pin "13") (pinfunction "PI11_13") (pintype "passive"))
    )
    (net (code "114") (name "/SDCKE1") (class "Default")
      (node (ref "U1") (pin "84") (pinfunction "PH7_84") (pintype "passive"))
      (node (ref "U2") (pin "37") (pinfunction "CKE_37") (pintype "passive"))
    )
    (net (code "115") (name "/SDCLK") (class "Default")
      (node (ref "U1") (pin "112") (pinfunction "PG8_112") (pintype "passive"))
      (node (ref "U2") (pin "38") (pinfunction "CLK_38") (pintype "passive"))
    )
    (net (code "116") (name "/SDNCAS") (class "Default")
      (node (ref "U1") (pin "160") (pinfunction "PG15_160") (pintype "passive"))
      (node (ref "U2") (pin "17") (pinfunction "CAS_17") (pintype "passive"))
    )
    (net (code "117") (name "/SDNE1") (class "Default")
      (node (ref "U1") (pin "83") (pinfunction "PH6_83") (pintype "passive"))
      (node (ref "U2") (pin "19") (pinfunction "CS_19") (pintype "passive"))
    )
    (net (code "118") (name "/SDNRAS") (class "Default")
      (node (ref "U1") (pin "59") (pinfunction "PF11_59") (pintype "passive"))
      (node (ref "U2") (pin "18") (pinfunction "RAS_18") (pintype "passive"))
    )
    (net (code "119") (name "/SDNWE") (class "Default")
      (node (ref "U1") (pin "32") (pinfunction "PC0_32") (pintype "passive"))
      (node (ref "U2") (pin "16") (pinfunction "WE_16") (pintype "passive"))
    )
    (net (code "120") (name "/SPI1_MISO") (class "Default")
      (node (ref "P4") (pin "4") (pinfunction "4_4") (pintype "passive"))
      (node (ref "U1") (pin "52") (pinfunction "PA6_52") (pintype "passive"))
    )
    (net (code "121") (name "/SPI1_MOSI") (class "Default")
      (node (ref "P4") (pin "24") (pinfunction "24_24") (pintype "passive"))
      (node (ref "U1") (pin "163") (pinfunction "PB5_163") (pintype "passive"))
    )
    (net (code "122") (name "/SPI1_NSS") (class "Default")
      (node (ref "P2") (pin "7") (pinfunction "7_7") (pintype "passive"))
      (node (ref "U1") (pin "138") (pinfunction "PA15_138") (pintype "passive"))
    )
    (net (code "123") (name "/SPI1_SCK") (class "Default")
      (node (ref "P4") (pin "6") (pinfunction "6_6") (pintype "passive"))
      (node (ref "U1") (pin "51") (pinfunction "PA5_51") (pintype "passive"))
    )
    (net (code "124") (name "/SPI2_MISO") (class "Default")
      (node (ref "P3") (pin "15") (pinfunction "15_15") (pintype "passive"))
      (node (ref "U1") (pin "34") (pinfunction "PC2_34") (pintype "passive"))
    )
    (net (code "125") (name "/SPI2_MOSI") (class "Default")
      (node (ref "P3") (pin "13") (pinfunction "13_13") (pintype "passive"))
      (node (ref "U1") (pin "35") (pinfunction "PC3_35") (pintype "passive"))
    )
    (net (code "126") (name "/SPI2_SCK") (class "Default")
      (node (ref "P1") (pin "15") (pinfunction "15_15") (pintype "passive"))
      (node (ref "U1") (pin "145") (pinfunction "PD3_145") (pintype "passive"))
    )
    (net (code "127") (name "/SPI3_MISO") (class "Default")
      (node (ref "P1") (pin "13") (pinfunction "13_13") (pintype "passive"))
      (node (ref "U1") (pin "162") (pinfunction "PB4_162") (pintype "passive"))
    )
    (net (code "128") (name "/SPI3_MOSI") (class "Default")
      (node (ref "P1") (pin "7") (pinfunction "7_7") (pintype "passive"))
      (node (ref "U1") (pin "141") (pinfunction "PC12_141") (pintype "passive"))
    )
    (net (code "129") (name "/SPI3_SCK") (class "Default")
      (node (ref "P1") (pin "5") (pinfunction "5_5") (pintype "passive"))
      (node (ref "U1") (pin "139") (pinfunction "PC10_139") (pintype "passive"))
    )
    (net (code "130") (name "/TOUCH_RESET") (class "Default")
      (node (ref "P3") (pin "19") (pinfunction "19_19") (pintype "passive"))
      (node (ref "U1") (pin "27") (pinfunction "PF9_27") (pintype "passive"))
    )
    (net (code "131") (name "/USART2_RX") (class "Default")
      (node (ref "P2") (pin "1") (pinfunction "1_1") (pintype "passive"))
      (node (ref "U1") (pin "150") (pinfunction "PD6_150") (pintype "passive"))
    )
    (net (code "132") (name "/USART2_TX") (class "Default")
      (node (ref "P2") (pin "8") (pinfunction "8_8") (pintype "passive"))
      (node (ref "U1") (pin "147") (pinfunction "PD5_147") (pintype "passive"))
    )
    (net (code "133") (name "/USART3_RX") (class "Default")
      (node (ref "P2") (pin "6") (pinfunction "6_6") (pintype "passive"))
      (node (ref "U1") (pin "140") (pinfunction "PC11_140") (pintype "passive"))
    )
    (net (code "134") (name "/USART3_TX") (class "Default")
      (node (ref "P2") (pin "28") (pinfunction "28_28") (pintype "passive"))
      (node (ref "U1") (pin "79") (pinfunction "PB10_79") (pintype "passive"))
    )
    (net (code "135") (name "/USART6_RX") (class "Default")
      (node (ref "P2") (pin "4") (pinfunction "4_4") (pintype "passive"))
      (node (ref "U1") (pin "152") (pinfunction "PG9_152") (pintype "passive"))
    )
    (net (code "136") (name "/USART6_TX") (class "Default")
      (node (ref "P2") (pin "14") (pinfunction "14_14") (pintype "passive"))
      (node (ref "U1") (pin "115") (pinfunction "PC6_115") (pintype "passive"))
    )
    (net (code "137") (name "/VBAT") (class "Default")
      (node (ref "P4") (pin "25") (pinfunction "25_25") (pintype "passive"))
      (node (ref "U1") (pin "6") (pinfunction "VBAT_6") (pintype "passive"))
    )
    (net (code "138") (name "/VBUS") (class "Default")
      (node (ref "P2") (pin "19") (pinfunction "19_19") (pintype "passive"))
      (node (ref "R3") (pin "2") (pinfunction "2_2") (pintype "passive"))
    )
    (net (code "139") (name "/WAKEUP") (class "Default")
      (node (ref "P4") (pin "7") (pinfunction "7_7") (pintype "passive"))
      (node (ref "U1") (pin "40") (pinfunction "WAKEUP/PA0_40") (pintype "passive"))
    )
    (net (code "140") (name "3V3") (class "Default")
      (node (ref "C1") (pin "2") (pinfunction "2_2") (pintype "passive"))
      (node (ref "C10") (pin "2") (pinfunction "2_2") (pintype "passive"))
      (node (ref "C11") (pin "2") (pinfunction "2_2") (pintype "passive"))
      (node (ref "C12") (pin "2") (pinfunction "2_2") (pintype "passive"))
      (node (ref "C13") (pin "2") (pinfunction "2_2") (pintype "passive"))
      (node (ref "C14") (pin "2") (pinfunction "2_2") (pintype "passive"))
      (node (ref "C15") (pin "2") (pinfunction "2_2") (pintype "passive"))
      (node (ref "C16") (pin "2") (pinfunction "2_2") (pintype "passive"))
      (node (ref "C17") (pin "2") (pinfunction "2_2") (pintype "passive"))
      (node (ref "C18") (pin "2") (pinfunction "2_2") (pintype "passive"))
      (node (ref "C19") (pin "2") (pinfunction "2_2") (pintype "passive"))
      (node (ref "C2") (pin "2") (pinfunction "2_2") (pintype "passive"))
      (node (ref "C20") (pin "2") (pinfunction "2_2") (pintype "passive"))
      (node (ref "C21") (pin "2") (pinfunction "2_2") (pintype "passive"))
      (node (ref "C22") (pin "2") (pinfunction "2_2") (pintype "passive"))
      (node (ref "C23") (pin "2") (pinfunction "2_2") (pintype "passive"))
      (node (ref "C25") (pin "2") (pinfunction "2_2") (pintype "passive"))
      (node (ref "C26") (pin "1") (pinfunction "1_1") (pintype "passive"))
      (node (ref "C27") (pin "2") (pinfunction "2_2") (pintype "passive"))
      (node (ref "C28") (pin "2") (pinfunction "2_2") (pintype "passive"))
      (node (ref "C29") (pin "2") (pinfunction "2_2") (pintype "passive"))
      (node (ref "C30") (pin "2") (pinfunction "2_2") (pintype "passive"))
      (node (ref "C31") (pin "2") (pinfunction "2_2") (pintype "passive"))
      (node (ref "C32") (pin "2") (pinfunction "2_2") (pintype "passive"))
      (node (ref "C33") (pin "2") (pinfunction "2_2") (pintype "passive"))
      (node (ref "C34") (pin "2") (pinfunction "2_2") (pintype "passive"))
      (node (ref "C6") (pin "2") (pinfunction "2_2") (pintype "passive"))
      (node (ref "C7") (pin "2") (pinfunction "2_2") (pintype "passive"))
      (node (ref "C8") (pin "2") (pinfunction "2_2") (pintype "passive"))
      (node (ref "C9") (pin "2") (pinfunction "2_2") (pintype "passive"))
      (node (ref "P3") (pin "5") (pinfunction "5_5") (pintype "passive"))
      (node (ref "P3") (pin "7") (pinfunction "7_7") (pintype "passive"))
      (node (ref "P4") (pin "12") (pinfunction "12_12") (pintype "passive"))
      (node (ref "P4") (pin "14") (pinfunction "14_14") (pintype "passive"))
      (node (ref "R2") (pin "1") (pinfunction "1_1") (pintype "passive"))
      (node (ref "U1") (pin "103") (pinfunction "VDD_103") (pintype "passive"))
      (node (ref "U1") (pin "114") (pinfunction "VDD_114") (pintype "passive"))
      (node (ref "U1") (pin "127") (pinfunction "VDD_127") (pintype "passive"))
      (node (ref "U1") (pin "136") (pinfunction "VDD_136") (pintype "passive"))
      (node (ref "U1") (pin "149") (pinfunction "VDD_149") (pintype "passive"))
      (node (ref "U1") (pin "15") (pinfunction "VDD_15") (pintype "passive"))
      (node (ref "U1") (pin "159") (pinfunction "VDD_159") (pintype "passive"))
      (node (ref "U1") (pin "171") (pinfunction "PDR_ON_171") (pintype "passive"))
      (node (ref "U1") (pin "172") (pinfunction "VDD_172") (pintype "passive"))
      (node (ref "U1") (pin "23") (pinfunction "VDD_23") (pintype "passive"))
      (node (ref "U1") (pin "36") (pinfunction "VDD_36") (pintype "passive"))
      (node (ref "U1") (pin "38") (pinfunction "VREF+_38") (pintype "passive"))
      (node (ref "U1") (pin "39") (pinfunction "VDDA_39") (pintype "passive"))
      (node (ref "U1") (pin "49") (pinfunction "VDD_49") (pintype "passive"))
      (node (ref "U1") (pin "62") (pinfunction "VDD_62") (pintype "passive"))
      (node (ref "U1") (pin "72") (pinfunction "VDD_72") (pintype "passive"))
      (node (ref "U1") (pin "82") (pinfunction "VDD_82") (pintype "passive"))
      (node (ref "U1") (pin "91") (pinfunction "VDD_91") (pintype "passive"))
      (node (ref "U2") (pin "1") (pinfunction "VDD_1") (pintype "passive"))
      (node (ref "U2") (pin "14") (pinfunction "VDD_14") (pintype "passive"))
      (node (ref "U2") (pin "27") (pinfunction "VDD_27") (pintype "passive"))
      (node (ref "U2") (pin "3") (pinfunction "VDDQ_3") (pintype "passive"))
      (node (ref "U2") (pin "43") (pinfunction "VDDQ_43") (pintype "passive"))
      (node (ref "U2") (pin "49") (pinfunction "VDDQ_49") (pintype "passive"))
      (node (ref "U2") (pin "9") (pinfunction "VDDQ_9") (pintype "passive"))
      (node (ref "U3") (pin "3") (pinfunction "VCC_3") (pintype "passive"))
      (node (ref "U4") (pin "5") (pinfunction "VOUT_5") (pintype "passive"))
      (node (ref "Y2") (pin "1") (pinfunction "EN_1") (pintype "passive"))
      (node (ref "Y2") (pin "4") (pinfunction "VCC_4") (pintype "passive"))
    )
    (net (code "141") (name "5V") (class "Default")
      (node (ref "C35") (pin "2") (pinfunction "2_2") (pintype "passive"))
      (node (ref "P3") (pin "1") (pinfunction "1_1") (pintype "passive"))
      (node (ref "P3") (pin "3") (pinfunction "3_3") (pintype "passive"))
      (node (ref "P4") (pin "18") (pinfunction "18_18") (pintype "passive"))
      (node (ref "P4") (pin "20") (pinfunction "20_20") (pintype "passive"))
      (node (ref "U4") (pin "1") (pinfunction "VIN_1") (pintype "passive"))
      (node (ref "U4") (pin "3") (pinfunction "CE_3") (pintype "passive"))
    )
    (net (code "142") (name "GND") (class "Default")
      (node (ref "C1") (pin "1") (pinfunction "1_1") (pintype "passive"))
      (node (ref "C10") (pin "1") (pinfunction "1_1") (pintype "passive"))
      (node (ref "C11") (pin "1") (pinfunction "1_1") (pintype "passive"))
      (node (ref "C12") (pin "1") (pinfunction "1_1") (pintype "passive"))
      (node (ref "C13") (pin "1") (pinfunction "1_1") (pintype "passive"))
      (node (ref "C14") (pin "1") (pinfunction "1_1") (pintype "passive"))
      (node (ref "C15") (pin "1") (pinfunction "1_1") (pintype "passive"))
      (node (ref "C16") (pin "1") (pinfunction "1_1") (pintype "passive"))
      (node (ref "C17") (pin "1") (pinfunction "1_1") (pintype "passive"))
      (node (ref "C18") (pin "1") (pinfunction "1_1") (pintype "passive"))
      (node (ref "C19") (pin "1") (pinfunction "1_1") (pintype "passive"))
      (node (ref "C2") (pin "1") (pinfunction "1_1") (pintype "passive"))
      (node (ref "C20") (pin "1") (pinfunction "1_1") (pintype "passive"))
      (node (ref "C21") (pin "1") (pinfunction "1_1") (pintype "passive"))
      (node (ref "C22") (pin "1") (pinfunction "1_1") (pintype "passive"))
      (node (ref "C23") (pin "1") (pinfunction "1_1") (pintype "passive"))
      (node (ref "C24") (pin "2") (pinfunction "2_2") (pintype "passive"))
      (node (ref "C25") (pin "1") (pinfunction "1_1") (pintype "passive"))
      (node (ref "C26") (pin "2") (pinfunction "2_2") (pintype "passive"))
      (node (ref "C27") (pin "1") (pinfunction "1_1") (pintype "passive"))
      (node (ref "C28") (pin "1") (pinfunction "1_1") (pintype "passive"))
      (node (ref "C29") (pin "1") (pinfunction "1_1") (pintype "passive"))
      (node (ref "C3") (pin "1") (pinfunction "1_1") (pintype "passive"))
      (node (ref "C30") (pin "1") (pinfunction "1_1") (pintype "passive"))
      (node (ref "C31") (pin "1") (pinfunction "1_1") (pintype "passive"))
      (node (ref "C32") (pin "1") (pinfunction "1_1") (pintype "passive"))
      (node (ref "C33") (pin "1") (pinfunction "1_1") (pintype "passive"))
      (node (ref "C34") (pin "1") (pinfunction "1_1") (pintype "passive"))
      (node (ref "C35") (pin "1") (pinfunction "1_1") (pintype "passive"))
      (node (ref "C4") (pin "1") (pinfunction "1_1") (pintype "passive"))
      (node (ref "C5") (pin "2") (pinfunction "2_2") (pintype "passive"))
      (node (ref "C6") (pin "1") (pinfunction "1_1") (pintype "passive"))
      (node (ref "C7") (pin "1") (pinfunction "1_1") (pintype "passive"))
      (node (ref "C8") (pin "1") (pinfunction "1_1") (pintype "passive"))
      (node (ref "C9") (pin "1") (pinfunction "1_1") (pintype "passive"))
      (node (ref "P2") (pin "25") (pinfunction "25_25") (pintype "passive"))
      (node (ref "P2") (pin "27") (pinfunction "27_27") (pintype "passive"))
      (node (ref "P3") (pin "26") (pinfunction "26_26") (pintype "passive"))
      (node (ref "P3") (pin "28") (pinfunction "28_28") (pintype "passive"))
      (node (ref "POWER") (pin "2") (pinfunction "K_2") (pintype "passive"))
      (node (ref "R1") (pin "2") (pinfunction "2_2") (pintype "passive"))
      (node (ref "R10") (pin "1") (pinfunction "1_1") (pintype "passive"))
      (node (ref "SYS1") (pin "2") (pinfunction "K_2") (pintype "passive"))
      (node (ref "U1") (pin "102") (pinfunction "VSS_102") (pintype "passive"))
      (node (ref "U1") (pin "113") (pinfunction "VSS_113") (pintype "passive"))
      (node (ref "U1") (pin "126") (pinfunction "VSS_126") (pintype "passive"))
      (node (ref "U1") (pin "135") (pinfunction "VSS_135") (pintype "passive"))
      (node (ref "U1") (pin "14") (pinfunction "VSS_14") (pintype "passive"))
      (node (ref "U1") (pin "148") (pinfunction "VSS_148") (pintype "passive"))
      (node (ref "U1") (pin "158") (pinfunction "VSS_158") (pintype "passive"))
      (node (ref "U1") (pin "22") (pinfunction "VSS_22") (pintype "passive"))
      (node (ref "U1") (pin "37") (pinfunction "VSSA_37") (pintype "passive"))
      (node (ref "U1") (pin "48") (pinfunction "BYPASS_REG_48") (pintype "passive"))
      (node (ref "U1") (pin "61") (pinfunction "VSS_61") (pintype "passive"))
      (node (ref "U1") (pin "71") (pinfunction "VSS_71") (pintype "passive"))
      (node (ref "U1") (pin "90") (pinfunction "VSS_90") (pintype "passive"))
      (node (ref "U2") (pin "12") (pinfunction "GNDQ_12") (pintype "passive"))
      (node (ref "U2") (pin "28") (pinfunction "GND_28") (pintype "passive"))
      (node (ref "U2") (pin "41") (pinfunction "GND_41") (pintype "passive"))
      (node (ref "U2") (pin "46") (pinfunction "GNDQ_46") (pintype "passive"))
      (node (ref "U2") (pin "52") (pinfunction "GNDQ_52") (pintype "passive"))
      (node (ref "U2") (pin "54") (pinfunction "GND_54") (pintype "passive"))
      (node (ref "U2") (pin "6") (pinfunction "GNDQ_6") (pintype "passive"))
      (node (ref "U3") (pin "2") (pinfunction "GND_2") (pintype "passive"))
      (node (ref "U4") (pin "2") (pinfunction "GND_2") (pintype "passive"))
      (node (ref "Y2") (pin "2") (pinfunction "GND_2") (pintype "passive"))
    )
    (net (code "143") (name "Net-(C5-Pad1)") (class "Default")
      (node (ref "C5") (pin "1") (pinfunction "1_1") (pintype "passive"))
      (node (ref "R5") (pin "2") (pinfunction "2_2") (pintype "passive"))
      (node (ref "Y1") (pin "2") (pintype "passive"))
    )
    (net (code "144") (name "Net-(C24-Pad1)") (class "Default")
      (node (ref "C24") (pin "1") (pinfunction "1_1") (pintype "passive"))
      (node (ref "R6") (pin "2") (pinfunction "2_2") (pintype "passive"))
      (node (ref "Y1") (pin "1") (pintype "passive"))
    )
    (net (code "145") (name "Net-(POWER-A)") (class "Default")
      (node (ref "POWER") (pin "1") (pinfunction "A_1") (pintype "passive"))
      (node (ref "R2") (pin "2") (pinfunction "2_2") (pintype "passive"))
    )
    (net (code "146") (name "Net-(R8-Pad2)") (class "Default")
      (node (ref "R8") (pin "2") (pinfunction "2_2") (pintype "passive"))
      (node (ref "R9") (pin "2") (pinfunction "2_2") (pintype "passive"))
    )
    (net (code "147") (name "Net-(SYS1-A)") (class "Default")
      (node (ref "R4") (pin "2") (pinfunction "2_2") (pintype "passive"))
      (node (ref "SYS1") (pin "1") (pinfunction "A_1") (pintype "passive"))
    )
    (net (code "148") (name "Net-(U1B-BOOT0)") (class "Default")
      (node (ref "R1") (pin "1") (pinfunction "1_1") (pintype "passive"))
      (node (ref "U1") (pin "166") (pinfunction "BOOT0_166") (pintype "passive"))
    )
    (net (code "149") (name "Net-(U1B-VCAP-1)") (class "Default")
      (node (ref "C4") (pin "2") (pinfunction "2_2") (pintype "passive"))
      (node (ref "U1") (pin "81") (pinfunction "VCAP-1_81") (pintype "passive"))
    )
    (net (code "150") (name "Net-(U1B-VCAP-2)") (class "Default")
      (node (ref "C3") (pin "2") (pinfunction "2_2") (pintype "passive"))
      (node (ref "U1") (pin "125") (pinfunction "VCAP-2_125") (pintype "passive"))
    )
    (net (code "151") (name "Net-(U1C-PA9)") (class "Default")
      (node (ref "R3") (pin "1") (pinfunction "1_1") (pintype "passive"))
      (node (ref "U1") (pin "120") (pinfunction "PA9_120") (pintype "passive"))
    )
    (net (code "152") (name "Net-(U3-RS)") (class "Default")
      (node (ref "R10") (pin "2") (pinfunction "2_2") (pintype "passive"))
      (node (ref "U3") (pin "8") (pinfunction "RS_8") (pintype "passive"))
    )
    (net (code "153") (name "Net-(Y2-OUT)") (class "Default")
      (node (ref "R7") (pin "1") (pinfunction "1_1") (pintype "passive"))
      (node (ref "Y2") (pin "3") (pinfunction "OUT_3") (pintype "passive"))
    )
    (net (code "154") (name "unconnected-(P2-Pad10)") (class "Default")
      (node (ref "P2") (pin "10") (pinfunction "10_10") (pintype "passive"))
    )
    (net (code "155") (name "unconnected-(P2-Pad12)") (class "Default")
      (node (ref "P2") (pin "12") (pinfunction "12_12") (pintype "passive"))
    )
    (net (code "156") (name "unconnected-(P2-Pad23)") (class "Default")
      (node (ref "P2") (pin "23") (pinfunction "23_23") (pintype "passive"))
    )
    (net (code "157") (name "unconnected-(P3-Pad6)") (class "Default")
      (node (ref "P3") (pin "6") (pinfunction "6_6") (pintype "passive"))
    )
    (net (code "158") (name "unconnected-(P3-Pad24)") (class "Default")
      (node (ref "P3") (pin "24") (pinfunction "24_24") (pintype "passive"))
    )
    (net (code "159") (name "unconnected-(U1B-PH1{slash}OSC_OUT-Pad30)") (class "Default")
      (node (ref "U1") (pin "30") (pinfunction "PH1/OSC_OUT_30") (pintype "passive+no_connect"))
    )
    (net (code "160") (name "unconnected-(U1C-PD13-Pad101)") (class "Default")
      (node (ref "U1") (pin "101") (pinfunction "PD13_101") (pintype "passive+no_connect"))
    )
    (net (code "161") (name "unconnected-(U1C-PE3-Pad2)") (class "Default")
      (node (ref "U1") (pin "2") (pinfunction "PE3_2") (pintype "passive"))
    )
    (net (code "162") (name "unconnected-(U1C-PG2-Pad106)") (class "Default")
      (node (ref "U1") (pin "106") (pinfunction "PG2_106") (pintype "passive+no_connect"))
    )
    (net (code "163") (name "unconnected-(U2-NC-Pad36)") (class "Default")
      (node (ref "U2") (pin "36") (pinfunction "NC_36") (pintype "passive+no_connect"))
    )
    (net (code "164") (name "unconnected-(U2-NC-Pad40)") (class "Default")
      (node (ref "U2") (pin "40") (pinfunction "NC_40") (pintype "passive+no_connect"))
    )
    (net (code "165") (name "unconnected-(U3-Vref-Pad5)") (class "Default")
      (node (ref "U3") (pin "5") (pinfunction "Vref_5") (pintype "passive+no_connect"))
    )
    (net (code "166") (name "unconnected-(U4-NC-Pad4)") (class "Default")
      (node (ref "U4") (pin "4") (pinfunction "NC_4") (pintype "passive+no_connect"))
    )
  )
)
